# tick-mk-4_6_4.net
KiCad netlist of a schematic drawn in EAGLE
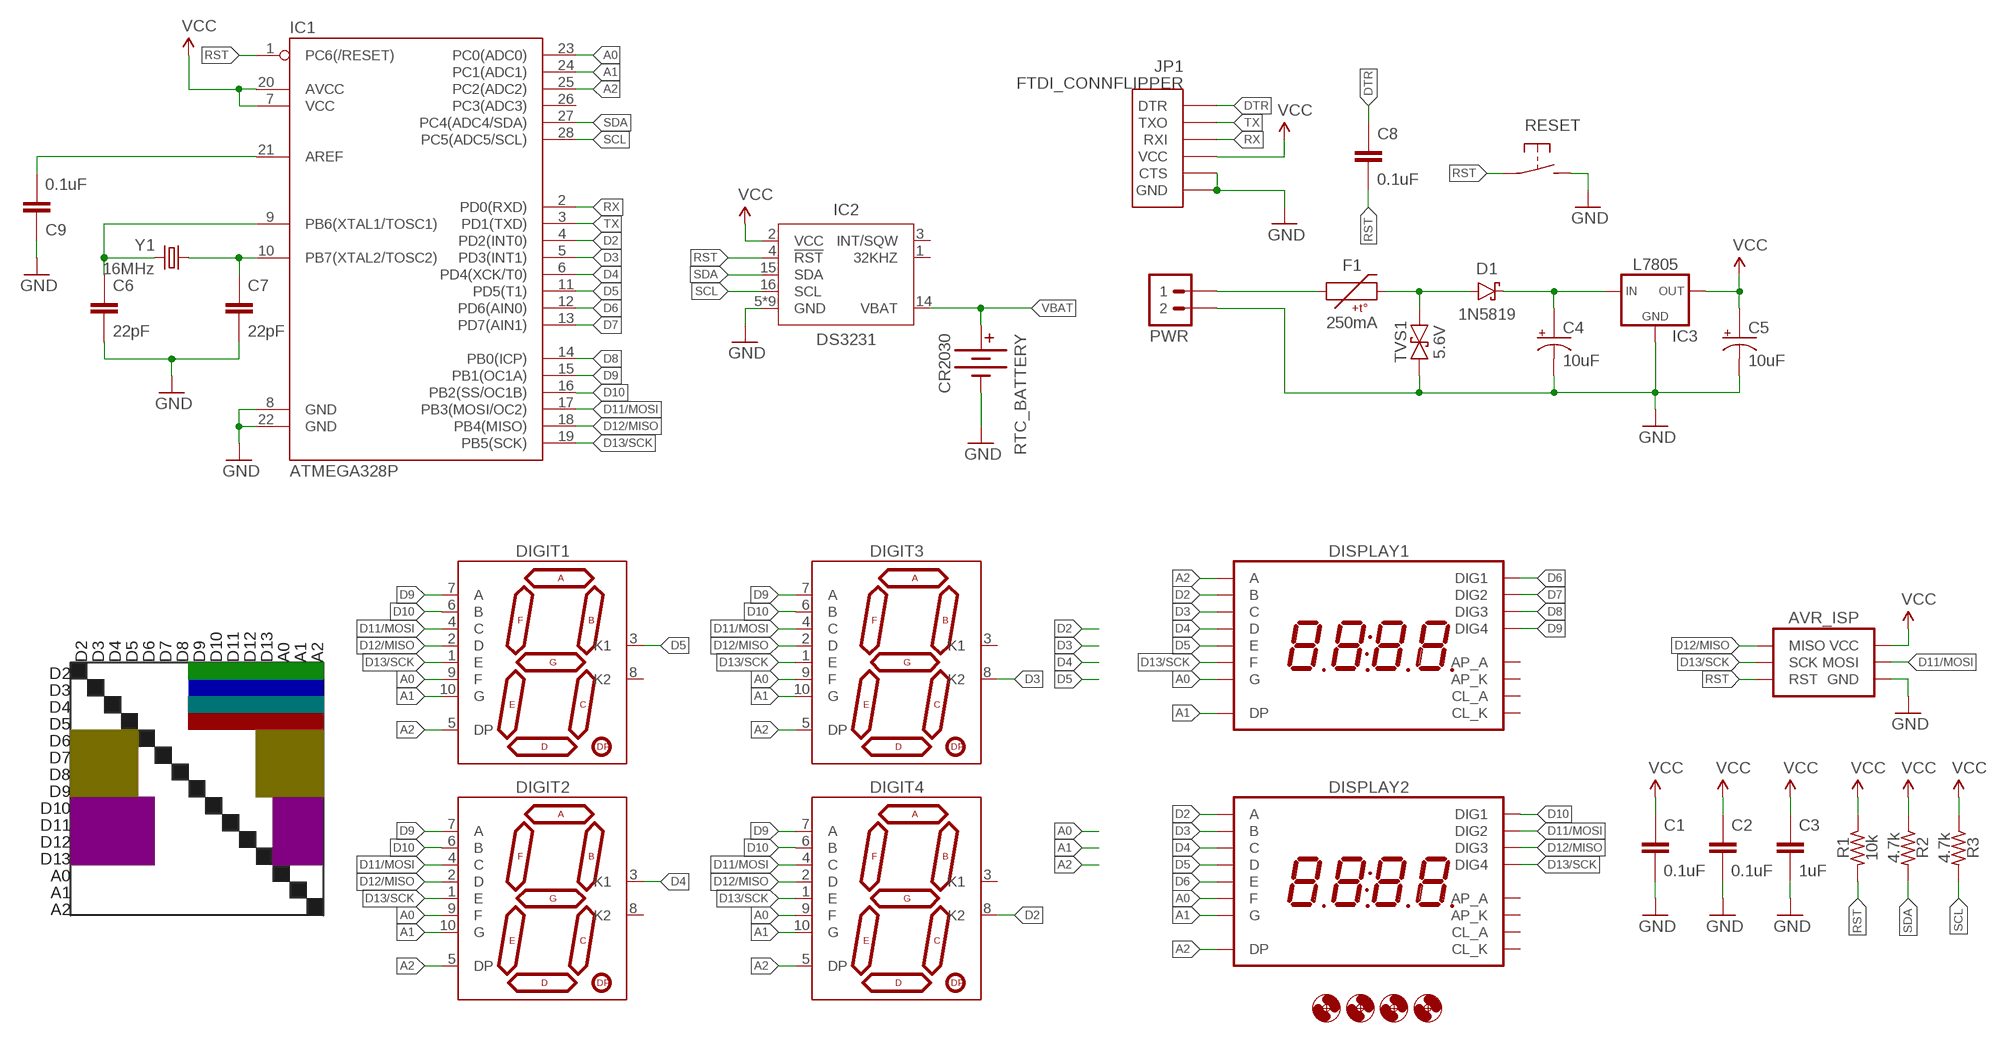
[diagram p0: schematic, sheet 1]

(export (version "E")
  (design (tool "Eeschema 10.0.6"))
  (components
    (comp (ref "AVR_ISP")
      (value "AVR_SPI_PRG_6PTH")
      (footprint "eagle-import:2X3")
      (libsource (lib "eagle-import") (part "AVR_SPI_PRG_6PTH"))
    )
    (comp (ref "C1")
      (value "0.1uF")
      (footprint "eagle-import:C025-024X044")
      (libsource (lib "eagle-import") (part "CAPACITOR-CERAMIC025-024X044"))
    )
    (comp (ref "C2")
      (value "0.1uF")
      (footprint "eagle-import:C025-024X044")
      (libsource (lib "eagle-import") (part "CAPACITOR-CERAMIC025-024X044"))
    )
    (comp (ref "C3")
      (value "1uF")
      (footprint "eagle-import:C025-024X044")
      (libsource (lib "eagle-import") (part "CAPACITOR-CERAMIC025-024X044"))
    )
    (comp (ref "C4")
      (value "10uF")
      (footprint "eagle-import:E2-5")
      (libsource (lib "eagle-import") (part "CAPACITOR-POLARIZEDE2-5"))
    )
    (comp (ref "C5")
      (value "10uF")
      (footprint "eagle-import:E2-5")
      (libsource (lib "eagle-import") (part "CAPACITOR-POLARIZEDE2-5"))
    )
    (comp (ref "C6")
      (value "22pF")
      (footprint "eagle-import:C025-024X044")
      (libsource (lib "eagle-import") (part "CAPACITOR-CERAMIC025-024X044"))
    )
    (comp (ref "C7")
      (value "22pF")
      (footprint "eagle-import:C025-024X044")
      (libsource (lib "eagle-import") (part "CAPACITOR-CERAMIC025-024X044"))
    )
    (comp (ref "C8")
      (value "0.1uF")
      (footprint "eagle-import:C025-024X044")
      (libsource (lib "eagle-import") (part "CAPACITOR-CERAMIC025-024X044"))
    )
    (comp (ref "C9")
      (value "0.1uF")
      (footprint "eagle-import:C025-024X044")
      (libsource (lib "eagle-import") (part "CAPACITOR-CERAMIC025-024X044"))
    )
    (comp (ref "D1")
      (value "1N5819")
      (footprint "eagle-import:DIODE-10.16MM")
      (libsource (lib "eagle-import") (part "DIODE-SCHOTTKYPTH-10.16MM"))
    )
    (comp (ref "DIGIT1")
      (value "7SEG_1DIGPTH-25.4MM-BARE")
      (footprint "eagle-import:7SEG_1DIG_25.4MM_NOSILK")
      (libsource (lib "eagle-import") (part "7SEG_1DIGPTH-25.4MM-BARE"))
    )
    (comp (ref "DIGIT2")
      (value "7SEG_1DIGPTH-25.4MM-BARE")
      (footprint "eagle-import:7SEG_1DIG_25.4MM_NOSILK")
      (libsource (lib "eagle-import") (part "7SEG_1DIGPTH-25.4MM-BARE"))
    )
    (comp (ref "DIGIT3")
      (value "7SEG_1DIGPTH-25.4MM-BARE")
      (footprint "eagle-import:7SEG_1DIG_25.4MM_NOSILK")
      (libsource (lib "eagle-import") (part "7SEG_1DIGPTH-25.4MM-BARE"))
    )
    (comp (ref "DIGIT4")
      (value "7SEG_1DIGPTH-25.4MM-BARE")
      (footprint "eagle-import:7SEG_1DIG_25.4MM_NOSILK")
      (libsource (lib "eagle-import") (part "7SEG_1DIGPTH-25.4MM-BARE"))
    )
    (comp (ref "DISPLAY1")
      (value "7SEG_4DIGIT_COLON_APOS")
      (footprint "eagle-import:7SEG_4DIG_10MM")
      (libsource (lib "eagle-import") (part "7SEG_4DIGIT_COLON_APOS"))
    )
    (comp (ref "DISPLAY2")
      (value "7SEG_4DIGIT_COLON_APOS")
      (footprint "eagle-import:7SEG_4DIG_10MM")
      (libsource (lib "eagle-import") (part "7SEG_4DIGIT_COLON_APOS"))
    )
    (comp (ref "F1")
      (value "250mA")
      (footprint "eagle-import:PTC-PTH-5.08MM")
      (libsource (lib "eagle-import") (part "PTCPTH-5.08MM"))
    )
    (comp (ref "H1")
      (value "HOLE#2")
      (footprint "eagle-import:HOLE-#2")
      (libsource (lib "eagle-import") (part "HOLE#2"))
    )
    (comp (ref "H2")
      (value "HOLE#2")
      (footprint "eagle-import:HOLE-#2")
      (libsource (lib "eagle-import") (part "HOLE#2"))
    )
    (comp (ref "H3")
      (value "HOLE#2")
      (footprint "eagle-import:HOLE-#2")
      (libsource (lib "eagle-import") (part "HOLE#2"))
    )
    (comp (ref "H4")
      (value "HOLE#2")
      (footprint "eagle-import:HOLE-#2")
      (libsource (lib "eagle-import") (part "HOLE#2"))
    )
    (comp (ref "IC1")
      (value "ATMEGA328P")
      (footprint "eagle-import:DIL28-3")
      (libsource (lib "eagle-import") (part "ATMEGA328P_PDIP"))
    )
    (comp (ref "IC2")
      (value "DS3231")
      (footprint "eagle-import:SO16W")
      (libsource (lib "eagle-import") (part "DS3231"))
    )
    (comp (ref "IC3")
      (value "L7805")
      (footprint "eagle-import:TO220-IGO-THERMPAD")
      (libsource (lib "eagle-import") (part "V_REG_78XXTO-220-THERMPAD"))
    )
    (comp (ref "JP1")
      (value "FTDI_CONNFLIPPER")
      (footprint "eagle-import:FTDI_CONN_FLIP")
      (libsource (lib "eagle-import") (part "FTDI_CONNFLIPPER"))
    )
    (comp (ref "PWR")
      (value "M02JST-PTH-VERT")
      (footprint "eagle-import:JST-2-PH-VERT-PTH")
      (libsource (lib "eagle-import") (part "M02JST-PTH-VERT"))
    )
    (comp (ref "R1")
      (value "10k")
      (footprint "eagle-import:RESISTOR-AXIAL-PTH-7.62MM")
      (libsource (lib "eagle-import") (part "RESISTORPTH-AXIAL-7.62MM"))
    )
    (comp (ref "R2")
      (value "4.7k")
      (footprint "eagle-import:RESISTOR-AXIAL-PTH-6.35MM")
      (libsource (lib "eagle-import") (part "RESISTORPTH-AXIAL-6.35MM"))
    )
    (comp (ref "R3")
      (value "4.7k")
      (footprint "eagle-import:RESISTOR-AXIAL-PTH-6.35MM")
      (libsource (lib "eagle-import") (part "RESISTORPTH-AXIAL-6.35MM"))
    )
    (comp (ref "RESET")
      (value "SPST-NO-TACT6MM-PTH-SMALL-PADS")
      (footprint "eagle-import:DTS-6-SMALL-PADS")
      (libsource (lib "eagle-import") (part "SPST-NO-TACT6MM-PTH-SMALL-PADS"))
    )
    (comp (ref "RTC_BATTERY")
      (value "CR2030")
      (footprint "eagle-import:BATTCON_20MM_MINE")
      (libsource (lib "eagle-import") (part "BATTERY20MMSMD-MINE"))
    )
    (comp (ref "TVS1")
      (value "5.6V")
      (footprint "eagle-import:DO-41-TVS-BI-10.16MM")
      (libsource (lib "eagle-import") (part "TVSDO-41-10.16MM"))
    )
    (comp (ref "Y1")
      (value "16MHz")
      (footprint "eagle-import:HC49U-V")
      (libsource (lib "eagle-import") (part "CRYSTALHC49UV"))
    )
  )
  (nets
    (net (code "1") (name "A0") (class "Default")
      (node (ref "DIGIT1") (pin "9") (pinfunction "F_9") (pintype "bidirectional"))
      (node (ref "DIGIT2") (pin "9") (pinfunction "F_9") (pintype "bidirectional"))
      (node (ref "DIGIT3") (pin "9") (pinfunction "F_9") (pintype "bidirectional"))
      (node (ref "DIGIT4") (pin "9") (pinfunction "F_9") (pintype "bidirectional"))
      (node (ref "DISPLAY1") (pin "15") (pinfunction "G_15") (pintype "passive"))
      (node (ref "DISPLAY2") (pin "11") (pinfunction "F_11") (pintype "passive"))
      (node (ref "IC1") (pin "23") (pinfunction "PC0(ADC0)_23") (pintype "bidirectional"))
    )
    (net (code "2") (name "A1") (class "Default")
      (node (ref "DIGIT1") (pin "10") (pinfunction "G_10") (pintype "bidirectional"))
      (node (ref "DIGIT2") (pin "10") (pinfunction "G_10") (pintype "bidirectional"))
      (node (ref "DIGIT3") (pin "10") (pinfunction "G_10") (pintype "bidirectional"))
      (node (ref "DIGIT4") (pin "10") (pinfunction "G_10") (pintype "bidirectional"))
      (node (ref "DISPLAY1") (pin "7") (pinfunction "DP_7") (pintype "passive"))
      (node (ref "DISPLAY2") (pin "15") (pinfunction "G_15") (pintype "passive"))
      (node (ref "IC1") (pin "24") (pinfunction "PC1(ADC1)_24") (pintype "bidirectional"))
    )
    (net (code "3") (name "A2") (class "Default")
      (node (ref "DIGIT1") (pin "5") (pinfunction "DP_5") (pintype "bidirectional"))
      (node (ref "DIGIT2") (pin "5") (pinfunction "DP_5") (pintype "bidirectional"))
      (node (ref "DIGIT3") (pin "5") (pinfunction "DP_5") (pintype "bidirectional"))
      (node (ref "DIGIT4") (pin "5") (pinfunction "DP_5") (pintype "bidirectional"))
      (node (ref "DISPLAY1") (pin "14") (pinfunction "A_14") (pintype "passive"))
      (node (ref "DISPLAY2") (pin "7") (pinfunction "DP_7") (pintype "passive"))
      (node (ref "IC1") (pin "25") (pinfunction "PC2(ADC2)_25") (pintype "bidirectional"))
    )
    (net (code "4") (name "D2") (class "Default")
      (node (ref "DIGIT4") (pin "8") (pinfunction "K2_8") (pintype "bidirectional"))
      (node (ref "DISPLAY1") (pin "16") (pinfunction "B_16") (pintype "passive"))
      (node (ref "DISPLAY2") (pin "14") (pinfunction "A_14") (pintype "passive"))
      (node (ref "IC1") (pin "4") (pinfunction "PD2(INT0)_4") (pintype "bidirectional"))
    )
    (net (code "5") (name "D3") (class "Default")
      (node (ref "DIGIT3") (pin "8") (pinfunction "K2_8") (pintype "bidirectional"))
      (node (ref "DISPLAY1") (pin "13") (pinfunction "C_13") (pintype "passive"))
      (node (ref "DISPLAY2") (pin "16") (pinfunction "B_16") (pintype "passive"))
      (node (ref "IC1") (pin "5") (pinfunction "PD3(INT1)_5") (pintype "bidirectional"))
    )
    (net (code "6") (name "D4") (class "Default")
      (node (ref "DIGIT2") (pin "3") (pinfunction "K1_3") (pintype "bidirectional"))
      (node (ref "DISPLAY1") (pin "3") (pinfunction "D_3") (pintype "passive"))
      (node (ref "DISPLAY2") (pin "13") (pinfunction "C_13") (pintype "passive"))
      (node (ref "IC1") (pin "6") (pinfunction "PD4(XCK/T0)_6") (pintype "bidirectional"))
    )
    (net (code "7") (name "D5") (class "Default")
      (node (ref "DIGIT1") (pin "3") (pinfunction "K1_3") (pintype "bidirectional"))
      (node (ref "DISPLAY1") (pin "5") (pinfunction "E_5") (pintype "passive"))
      (node (ref "DISPLAY2") (pin "3") (pinfunction "D_3") (pintype "passive"))
      (node (ref "IC1") (pin "11") (pinfunction "PD5(T1)_11") (pintype "bidirectional"))
    )
    (net (code "8") (name "D6") (class "Default")
      (node (ref "DISPLAY1") (pin "1") (pinfunction "DIG1_1") (pintype "passive"))
      (node (ref "DISPLAY2") (pin "5") (pinfunction "E_5") (pintype "passive"))
      (node (ref "IC1") (pin "12") (pinfunction "PD6(AIN0)_12") (pintype "bidirectional"))
    )
    (net (code "9") (name "D7") (class "Default")
      (node (ref "DISPLAY1") (pin "2") (pinfunction "DIG2_2") (pintype "passive"))
      (node (ref "IC1") (pin "13") (pinfunction "PD7(AIN1)_13") (pintype "bidirectional"))
    )
    (net (code "10") (name "D8") (class "Default")
      (node (ref "DISPLAY1") (pin "6") (pinfunction "DIG3_6") (pintype "passive"))
      (node (ref "IC1") (pin "14") (pinfunction "PB0(ICP)_14") (pintype "bidirectional"))
    )
    (net (code "11") (name "D9") (class "Default")
      (node (ref "DIGIT1") (pin "7") (pinfunction "A_7") (pintype "bidirectional"))
      (node (ref "DIGIT2") (pin "7") (pinfunction "A_7") (pintype "bidirectional"))
      (node (ref "DIGIT3") (pin "7") (pinfunction "A_7") (pintype "bidirectional"))
      (node (ref "DIGIT4") (pin "7") (pinfunction "A_7") (pintype "bidirectional"))
      (node (ref "DISPLAY1") (pin "8") (pinfunction "DIG4_8") (pintype "passive"))
      (node (ref "IC1") (pin "15") (pinfunction "PB1(OC1A)_15") (pintype "bidirectional"))
    )
    (net (code "12") (name "D10") (class "Default")
      (node (ref "DIGIT1") (pin "6") (pinfunction "B_6") (pintype "bidirectional"))
      (node (ref "DIGIT2") (pin "6") (pinfunction "B_6") (pintype "bidirectional"))
      (node (ref "DIGIT3") (pin "6") (pinfunction "B_6") (pintype "bidirectional"))
      (node (ref "DIGIT4") (pin "6") (pinfunction "B_6") (pintype "bidirectional"))
      (node (ref "DISPLAY2") (pin "1") (pinfunction "DIG1_1") (pintype "passive"))
      (node (ref "IC1") (pin "16") (pinfunction "PB2(SS/OC1B)_16") (pintype "bidirectional"))
    )
    (net (code "13") (name "D11{slash}MOSI") (class "Default")
      (node (ref "AVR_ISP") (pin "4") (pinfunction "MOSI_4") (pintype "passive"))
      (node (ref "DIGIT1") (pin "4") (pinfunction "C_4") (pintype "bidirectional"))
      (node (ref "DIGIT2") (pin "4") (pinfunction "C_4") (pintype "bidirectional"))
      (node (ref "DIGIT3") (pin "4") (pinfunction "C_4") (pintype "bidirectional"))
      (node (ref "DIGIT4") (pin "4") (pinfunction "C_4") (pintype "bidirectional"))
      (node (ref "DISPLAY2") (pin "2") (pinfunction "DIG2_2") (pintype "passive"))
      (node (ref "IC1") (pin "17") (pinfunction "PB3(MOSI/OC2)_17") (pintype "bidirectional"))
    )
    (net (code "14") (name "D12{slash}MISO") (class "Default")
      (node (ref "AVR_ISP") (pin "1") (pinfunction "MISO_1") (pintype "passive"))
      (node (ref "DIGIT1") (pin "2") (pinfunction "D_2") (pintype "bidirectional"))
      (node (ref "DIGIT2") (pin "2") (pinfunction "D_2") (pintype "bidirectional"))
      (node (ref "DIGIT3") (pin "2") (pinfunction "D_2") (pintype "bidirectional"))
      (node (ref "DIGIT4") (pin "2") (pinfunction "D_2") (pintype "bidirectional"))
      (node (ref "DISPLAY2") (pin "6") (pinfunction "DIG3_6") (pintype "passive"))
      (node (ref "IC1") (pin "18") (pinfunction "PB4(MISO)_18") (pintype "bidirectional"))
    )
    (net (code "15") (name "D13{slash}SCK") (class "Default")
      (node (ref "AVR_ISP") (pin "3") (pinfunction "SCK_3") (pintype "passive"))
      (node (ref "DIGIT1") (pin "1") (pinfunction "E_1") (pintype "bidirectional"))
      (node (ref "DIGIT2") (pin "1") (pinfunction "E_1") (pintype "bidirectional"))
      (node (ref "DIGIT3") (pin "1") (pinfunction "E_1") (pintype "bidirectional"))
      (node (ref "DIGIT4") (pin "1") (pinfunction "E_1") (pintype "bidirectional"))
      (node (ref "DISPLAY1") (pin "11") (pinfunction "F_11") (pintype "passive"))
      (node (ref "DISPLAY2") (pin "8") (pinfunction "DIG4_8") (pintype "passive"))
      (node (ref "IC1") (pin "19") (pinfunction "PB5(SCK)_19") (pintype "bidirectional"))
    )
    (net (code "16") (name "DTR") (class "Default")
      (node (ref "C8") (pin "1") (pinfunction "1_1") (pintype "passive"))
      (node (ref "JP1") (pin "DTR") (pinfunction "DTR_DTR") (pintype "bidirectional"))
    )
    (net (code "17") (name "GND") (class "Default")
      (node (ref "AVR_ISP") (pin "6") (pinfunction "GND_6") (pintype "passive"))
      (node (ref "C1") (pin "2") (pinfunction "2_2") (pintype "passive"))
      (node (ref "C2") (pin "2") (pinfunction "2_2") (pintype "passive"))
      (node (ref "C3") (pin "2") (pinfunction "2_2") (pintype "passive"))
      (node (ref "C4") (pin "-") (pinfunction "-_-") (pintype "passive"))
      (node (ref "C5") (pin "-") (pinfunction "-_-") (pintype "passive"))
      (node (ref "C6") (pin "2") (pinfunction "2_2") (pintype "passive"))
      (node (ref "C7") (pin "2") (pinfunction "2_2") (pintype "passive"))
      (node (ref "C9") (pin "1") (pinfunction "1_1") (pintype "passive"))
      (node (ref "IC1") (pin "22") (pinfunction "GND_22") (pintype "bidirectional"))
      (node (ref "IC1") (pin "8") (pinfunction "GND_8") (pintype "bidirectional"))
      (node (ref "IC2") (pin "10") (pinfunction "GND_10") (pintype "bidirectional"))
      (node (ref "IC2") (pin "11") (pinfunction "GND_11") (pintype "bidirectional"))
      (node (ref "IC2") (pin "12") (pinfunction "GND_12") (pintype "bidirectional"))
      (node (ref "IC2") (pin "13") (pinfunction "GND_13") (pintype "bidirectional"))
      (node (ref "IC2") (pin "5") (pinfunction "GND_5") (pintype "bidirectional"))
      (node (ref "IC2") (pin "6") (pinfunction "GND_6") (pintype "bidirectional"))
      (node (ref "IC2") (pin "7") (pinfunction "GND_7") (pintype "bidirectional"))
      (node (ref "IC2") (pin "8") (pinfunction "GND_8") (pintype "bidirectional"))
      (node (ref "IC2") (pin "9") (pinfunction "GND_9") (pintype "bidirectional"))
      (node (ref "IC3") (pin "4") (pinfunction "GND_4") (pintype "bidirectional"))
      (node (ref "IC3") (pin "GND") (pinfunction "GND_GND") (pintype "bidirectional"))
      (node (ref "JP1") (pin "CTS") (pinfunction "CTS_CTS") (pintype "bidirectional"))
      (node (ref "JP1") (pin "GND") (pinfunction "GND_GND") (pintype "bidirectional"))
      (node (ref "PWR") (pin "2") (pinfunction "2_2") (pintype "passive"))
      (node (ref "RESET") (pin "3") (pinfunction "2_3") (pintype "passive"))
      (node (ref "RESET") (pin "4") (pinfunction "2_4") (pintype "passive"))
      (node (ref "RTC_BATTERY") (pin "BOTTOM") (pinfunction "-_BOTTOM") (pintype "power_in"))
      (node (ref "TVS1") (pin "P$1") (pinfunction "1_P$1") (pintype "passive"))
    )
    (net (code "18") (name "Net-(C4-Pad+)") (class "Default")
      (node (ref "C4") (pin "+") (pinfunction "+_+") (pintype "passive"))
      (node (ref "D1") (pin "C") (pinfunction "C_C") (pintype "passive"))
      (node (ref "IC3") (pin "IN") (pinfunction "IN_IN") (pintype "bidirectional"))
    )
    (net (code "19") (name "Net-(F1-1)") (class "Default")
      (node (ref "F1") (pin "P$1") (pinfunction "1_P$1") (pintype "passive"))
      (node (ref "PWR") (pin "1") (pinfunction "1_1") (pintype "passive"))
    )
    (net (code "20") (name "Net-(F1-2)") (class "Default")
      (node (ref "D1") (pin "A") (pinfunction "A_A") (pintype "passive"))
      (node (ref "F1") (pin "P$2") (pinfunction "2_P$2") (pintype "passive"))
      (node (ref "TVS1") (pin "P$2") (pinfunction "2_P$2") (pintype "passive"))
    )
    (net (code "21") (name "Net-(IC1-AREF)") (class "Default")
      (node (ref "C9") (pin "2") (pinfunction "2_2") (pintype "passive"))
      (node (ref "IC1") (pin "21") (pinfunction "AREF_21") (pintype "bidirectional"))
    )
    (net (code "22") (name "Net-(IC1-PB6(XTAL1{slash}TOSC1))") (class "Default")
      (node (ref "C6") (pin "1") (pinfunction "1_1") (pintype "passive"))
      (node (ref "IC1") (pin "9") (pinfunction "PB6(XTAL1/TOSC1)_9") (pintype "bidirectional"))
      (node (ref "Y1") (pin "2") (pinfunction "2_2") (pintype "passive"))
    )
    (net (code "23") (name "Net-(IC1-PB7(XTAL2{slash}TOSC2))") (class "Default")
      (node (ref "C7") (pin "1") (pinfunction "1_1") (pintype "passive"))
      (node (ref "IC1") (pin "10") (pinfunction "PB7(XTAL2/TOSC2)_10") (pintype "bidirectional"))
      (node (ref "Y1") (pin "1") (pinfunction "1_1") (pintype "passive"))
    )
    (net (code "24") (name "RST") (class "Default")
      (node (ref "AVR_ISP") (pin "5") (pinfunction "RST_5") (pintype "passive"))
      (node (ref "C8") (pin "2") (pinfunction "2_2") (pintype "passive"))
      (node (ref "IC1") (pin "1") (pinfunction "PC6(/RESET)_1") (pintype "bidirectional"))
      (node (ref "IC2") (pin "4") (pinfunction "~{RST}_4") (pintype "bidirectional"))
      (node (ref "R1") (pin "P$2") (pinfunction "2_P$2") (pintype "passive"))
      (node (ref "RESET") (pin "1") (pinfunction "1_1") (pintype "passive"))
      (node (ref "RESET") (pin "2") (pinfunction "1_2") (pintype "passive"))
    )
    (net (code "25") (name "RX") (class "Default")
      (node (ref "IC1") (pin "2") (pinfunction "PD0(RXD)_2") (pintype "bidirectional"))
      (node (ref "JP1") (pin "RXI") (pinfunction "RXI_RXI") (pintype "bidirectional"))
    )
    (net (code "26") (name "SCL") (class "Default")
      (node (ref "IC1") (pin "28") (pinfunction "PC5(ADC5/SCL)_28") (pintype "bidirectional"))
      (node (ref "IC2") (pin "16") (pinfunction "SCL_16") (pintype "bidirectional"))
      (node (ref "R3") (pin "P$2") (pinfunction "2_P$2") (pintype "passive"))
    )
    (net (code "27") (name "SDA") (class "Default")
      (node (ref "IC1") (pin "27") (pinfunction "PC4(ADC4/SDA)_27") (pintype "bidirectional"))
      (node (ref "IC2") (pin "15") (pinfunction "SDA_15") (pintype "bidirectional"))
      (node (ref "R2") (pin "P$2") (pinfunction "2_P$2") (pintype "passive"))
    )
    (net (code "28") (name "TX") (class "Default")
      (node (ref "IC1") (pin "3") (pinfunction "PD1(TXD)_3") (pintype "bidirectional"))
      (node (ref "JP1") (pin "TXO") (pinfunction "TXO_TXO") (pintype "bidirectional"))
    )
    (net (code "29") (name "VBAT") (class "Default")
      (node (ref "IC2") (pin "14") (pinfunction "VBAT_14") (pintype "bidirectional"))
      (node (ref "RTC_BATTERY") (pin "TOP@1") (pinfunction "+_TOP@1") (pintype "power_in"))
      (node (ref "RTC_BATTERY") (pin "TOP@2") (pinfunction "+_TOP@2") (pintype "power_in"))
    )
    (net (code "30") (name "VCC") (class "Default")
      (node (ref "AVR_ISP") (pin "2") (pinfunction "VCC_2") (pintype "passive"))
      (node (ref "C1") (pin "1") (pinfunction "1_1") (pintype "passive"))
      (node (ref "C2") (pin "1") (pinfunction "1_1") (pintype "passive"))
      (node (ref "C3") (pin "1") (pinfunction "1_1") (pintype "passive"))
      (node (ref "C5") (pin "+") (pinfunction "+_+") (pintype "passive"))
      (node (ref "IC1") (pin "20") (pinfunction "AVCC_20") (pintype "bidirectional"))
      (node (ref "IC1") (pin "7") (pinfunction "VCC_7") (pintype "bidirectional"))
      (node (ref "IC2") (pin "2") (pinfunction "VCC_2") (pintype "bidirectional"))
      (node (ref "IC3") (pin "OUT") (pinfunction "OUT_OUT") (pintype "bidirectional"))
      (node (ref "JP1") (pin "VCC") (pinfunction "VCC_VCC") (pintype "bidirectional"))
      (node (ref "R1") (pin "P$1") (pinfunction "1_P$1") (pintype "passive"))
      (node (ref "R2") (pin "P$1") (pinfunction "1_P$1") (pintype "passive"))
      (node (ref "R3") (pin "P$1") (pinfunction "1_P$1") (pintype "passive"))
    )
    (net (code "31") (name "unconnected-(DIGIT1-K2-Pad8)") (class "Default")
      (node (ref "DIGIT1") (pin "8") (pinfunction "K2_8") (pintype "bidirectional"))
    )
    (net (code "32") (name "unconnected-(DIGIT2-K2-Pad8)") (class "Default")
      (node (ref "DIGIT2") (pin "8") (pinfunction "K2_8") (pintype "bidirectional"))
    )
    (net (code "33") (name "unconnected-(DIGIT3-K1-Pad3)") (class "Default")
      (node (ref "DIGIT3") (pin "3") (pinfunction "K1_3") (pintype "bidirectional"))
    )
    (net (code "34") (name "unconnected-(DIGIT4-K1-Pad3)") (class "Default")
      (node (ref "DIGIT4") (pin "3") (pinfunction "K1_3") (pintype "bidirectional"))
    )
    (net (code "35") (name "unconnected-(DISPLAY1-AP_A-Pad10)") (class "Default")
      (node (ref "DISPLAY1") (pin "10") (pinfunction "AP_A_10") (pintype "bidirectional"))
    )
    (net (code "36") (name "unconnected-(DISPLAY1-AP_K-Pad9)") (class "Default")
      (node (ref "DISPLAY1") (pin "9") (pinfunction "AP_K_9") (pintype "bidirectional"))
    )
    (net (code "37") (name "unconnected-(DISPLAY1-CL_A-Pad4)") (class "Default")
      (node (ref "DISPLAY1") (pin "4") (pinfunction "CL_A_4") (pintype "passive"))
    )
    (net (code "38") (name "unconnected-(DISPLAY1-CL_K-Pad12)") (class "Default")
      (node (ref "DISPLAY1") (pin "12") (pinfunction "CL_K_12") (pintype "passive"))
    )
    (net (code "39") (name "unconnected-(DISPLAY2-AP_A-Pad10)") (class "Default")
      (node (ref "DISPLAY2") (pin "10") (pinfunction "AP_A_10") (pintype "bidirectional"))
    )
    (net (code "40") (name "unconnected-(DISPLAY2-AP_K-Pad9)") (class "Default")
      (node (ref "DISPLAY2") (pin "9") (pinfunction "AP_K_9") (pintype "bidirectional"))
    )
    (net (code "41") (name "unconnected-(DISPLAY2-CL_A-Pad4)") (class "Default")
      (node (ref "DISPLAY2") (pin "4") (pinfunction "CL_A_4") (pintype "passive"))
    )
    (net (code "42") (name "unconnected-(DISPLAY2-CL_K-Pad12)") (class "Default")
      (node (ref "DISPLAY2") (pin "12") (pinfunction "CL_K_12") (pintype "passive"))
    )
    (net (code "43") (name "unconnected-(IC1-PC3(ADC3)-Pad26)") (class "Default")
      (node (ref "IC1") (pin "26") (pinfunction "PC3(ADC3)_26") (pintype "bidirectional"))
    )
    (net (code "44") (name "unconnected-(IC2-32KHZ-Pad1)") (class "Default")
      (node (ref "IC2") (pin "1") (pinfunction "32KHZ_1") (pintype "bidirectional"))
    )
    (net (code "45") (name "unconnected-(IC2-INT{slash}SQW-Pad3)") (class "Default")
      (node (ref "IC2") (pin "3") (pinfunction "INT/SQW_3") (pintype "bidirectional"))
    )
  )
)
